# Basisboard_Klemme.net
KiCad netlist of a schematic drawn in EAGLE
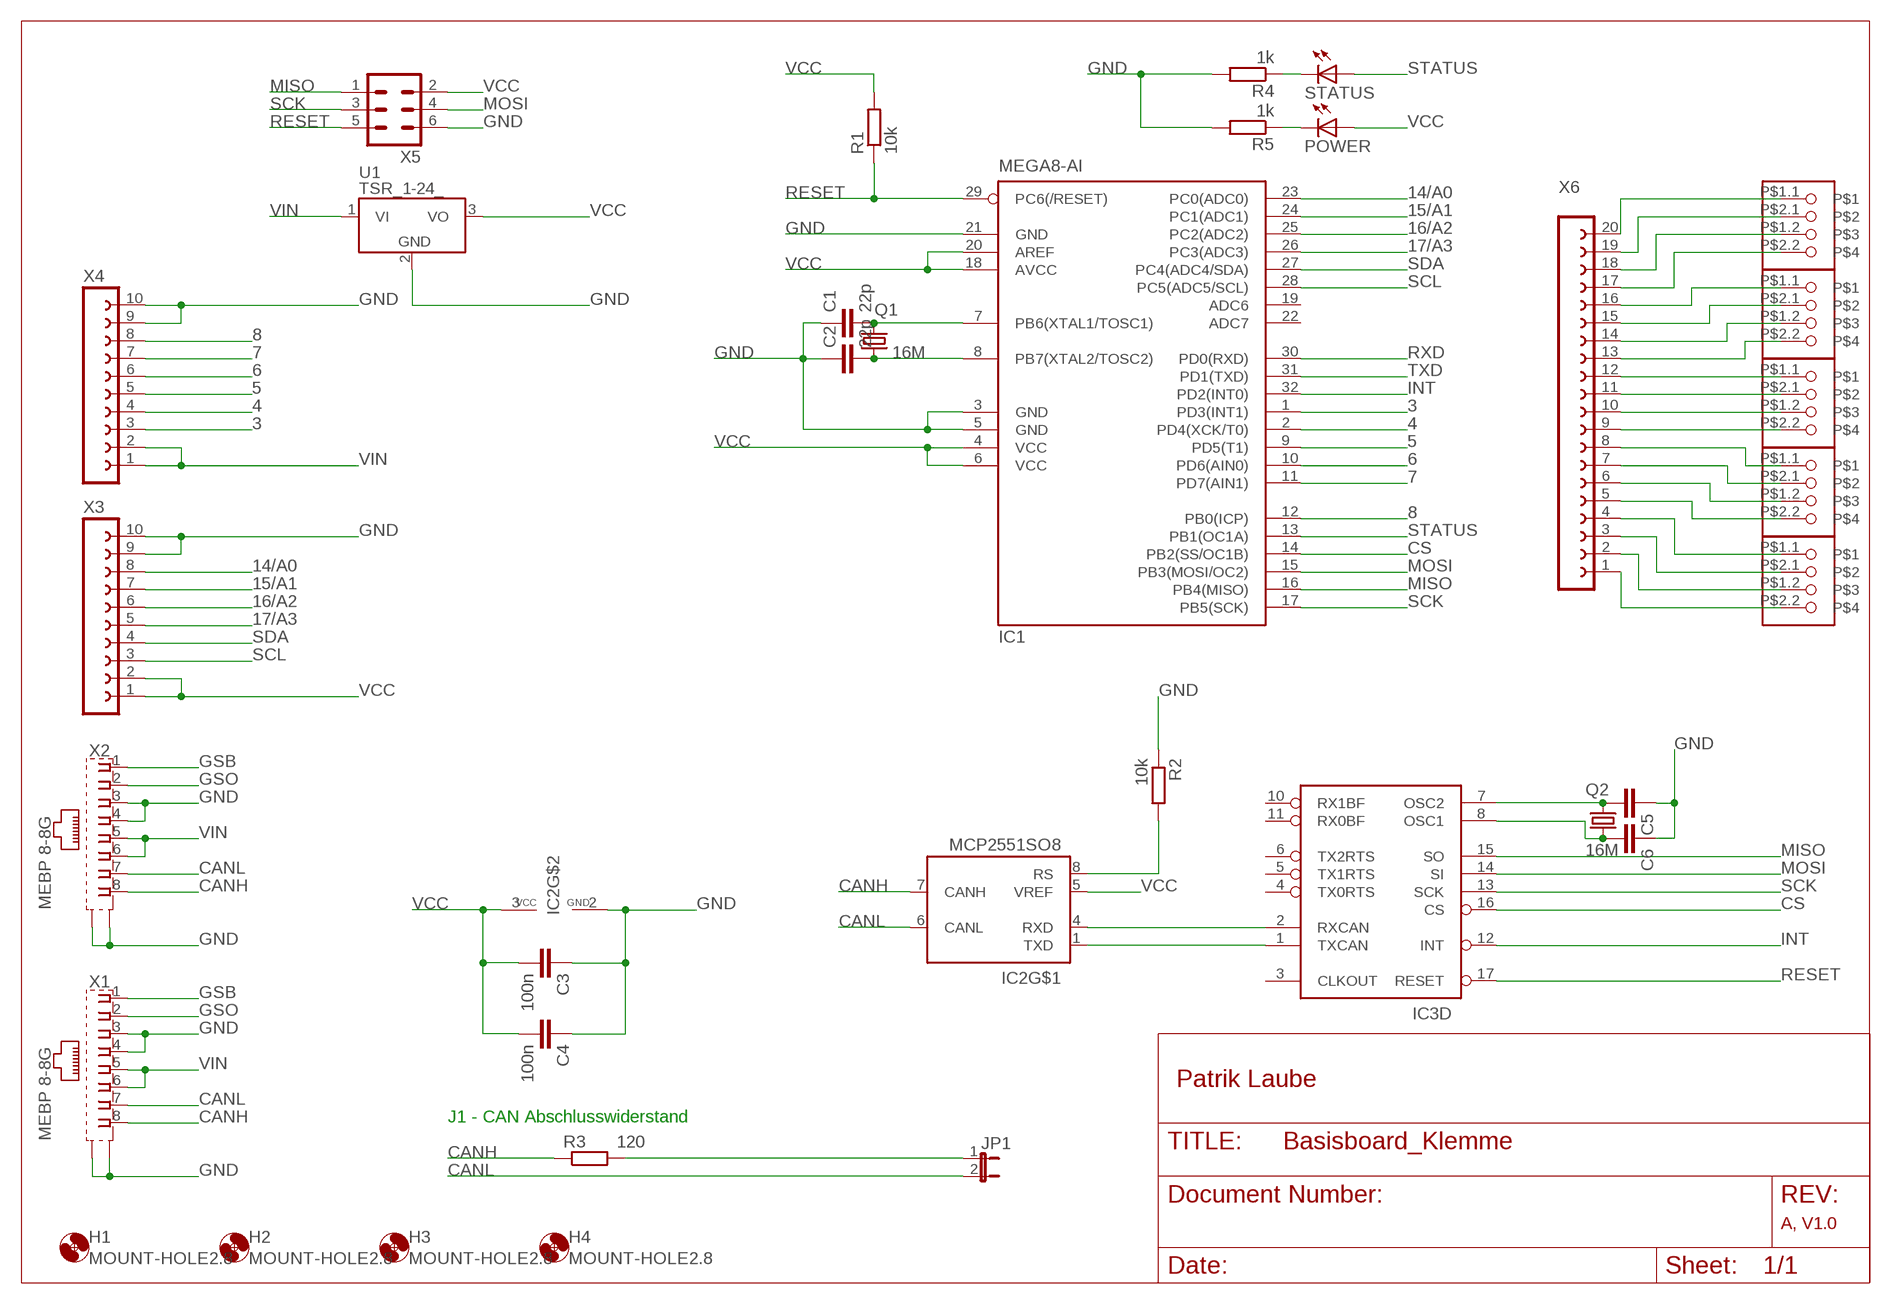
[diagram p0: schematic, sheet 1]

(export (version "E")
  (design (tool "Eeschema 10.0.6"))
  (components
    (comp (ref "C1")
      (value "22p")
      (footprint "eagle-import:C1206")
      (fields (field (name "LCSC_PART") "C313096"))
      (libsource (lib "eagle-import") (part "C-EUC1206"))
    )
    (comp (ref "C2")
      (value "22p")
      (footprint "eagle-import:C1206")
      (fields (field (name "LCSC_PART") "C313096"))
      (libsource (lib "eagle-import") (part "C-EUC1206"))
    )
    (comp (ref "C3")
      (value "100n")
      (footprint "eagle-import:C1206")
      (fields (field (name "LCSC_PART") "C24497"))
      (libsource (lib "eagle-import") (part "C-EUC1206"))
    )
    (comp (ref "C4")
      (value "100n")
      (footprint "eagle-import:C1206")
      (fields (field (name "LCSC_PART") "C24497"))
      (libsource (lib "eagle-import") (part "C-EUC1206"))
    )
    (comp (ref "C5")
      (value "C-EUC1206")
      (footprint "eagle-import:C1206")
      (fields (field (name "LCSC_PART") "C313096"))
      (libsource (lib "eagle-import") (part "C-EUC1206"))
    )
    (comp (ref "C6")
      (value "C-EUC1206")
      (footprint "eagle-import:C1206")
      (fields (field (name "LCSC_PART") "C313096"))
      (libsource (lib "eagle-import") (part "C-EUC1206"))
    )
    (comp (ref "H1")
      (value "MOUNT-HOLE2.8")
      (footprint "eagle-import:2,8")
      (libsource (lib "eagle-import") (part "MOUNT-HOLE2.8"))
    )
    (comp (ref "H2")
      (value "MOUNT-HOLE2.8")
      (footprint "eagle-import:2,8")
      (libsource (lib "eagle-import") (part "MOUNT-HOLE2.8"))
    )
    (comp (ref "H3")
      (value "MOUNT-HOLE2.8")
      (footprint "eagle-import:2,8")
      (libsource (lib "eagle-import") (part "MOUNT-HOLE2.8"))
    )
    (comp (ref "H4")
      (value "MOUNT-HOLE2.8")
      (footprint "eagle-import:2,8")
      (libsource (lib "eagle-import") (part "MOUNT-HOLE2.8"))
    )
    (comp (ref "IC1")
      (value "MEGA8-AI")
      (footprint "eagle-import:TQFP32-08")
      (fields (field (name "MPN") "ATMEGA8-16AU") (field (name "LCSC_PART") "C132230"))
      (libsource (lib "eagle-import") (part "MEGA8-AI"))
    )
    (comp (ref "IC2")
      (value "MCP2551SO8")
      (footprint "eagle-import:SO08")
      (fields (field (name "LCSC_PART") "C49558"))
      (libsource (lib "eagle-import") (part "MCP2551SO8"))
    )
    (comp (ref "IC3")
      (value "MCP2515SO")
      (footprint "eagle-import:SO-18W")
      (fields (field (name "LCSC_PART") "C153782"))
      (libsource (lib "eagle-import") (part "MCP2515SO"))
    )
    (comp (ref "JP1")
      (value "JP1E")
      (footprint "eagle-import:JP1")
      (libsource (lib "eagle-import") (part "JP1E"))
    )
    (comp (ref "POWER")
      (value "LEDCHIPLED_1206")
      (footprint "eagle-import:CHIPLED_1206")
      (fields (field (name "LCSC_PART") "C88326"))
      (libsource (lib "eagle-import") (part "LEDCHIPLED_1206"))
    )
    (comp (ref "Q1")
      (value "16M")
      (footprint "eagle-import:HC49_S")
      (libsource (lib "eagle-import") (part "CRYSTALHC49S"))
    )
    (comp (ref "Q2")
      (value "16M")
      (footprint "eagle-import:HC49_S")
      (libsource (lib "eagle-import") (part "CRYSTALHC49S"))
    )
    (comp (ref "R1")
      (value "10k")
      (footprint "eagle-import:R1206")
      (fields (field (name "LCSC_PART") " C17902"))
      (libsource (lib "eagle-import") (part "R-EU_R1206"))
    )
    (comp (ref "R2")
      (value "10k")
      (footprint "eagle-import:R1206")
      (fields (field (name "LCSC_PART") " C17902"))
      (libsource (lib "eagle-import") (part "R-EU_R1206"))
    )
    (comp (ref "R3")
      (value "120")
      (footprint "eagle-import:R1206")
      (fields (field (name "LCSC_PART") "C17909"))
      (libsource (lib "eagle-import") (part "rcl_334_R-EU_R1206"))
    )
    (comp (ref "R4")
      (value "1k")
      (footprint "eagle-import:R1206")
      (fields (field (name "LCSC_PART") "C4410"))
      (libsource (lib "eagle-import") (part "R-EU_R1206"))
    )
    (comp (ref "R5")
      (value "1k")
      (footprint "eagle-import:R1206")
      (fields (field (name "LCSC_PART") "C4410"))
      (libsource (lib "eagle-import") (part "R-EU_R1206"))
    )
    (comp (ref "STATUS")
      (value "LEDCHIPLED_1206")
      (footprint "eagle-import:CHIPLED_1206")
      (fields (field (name "LCSC_PART") "C84273"))
      (libsource (lib "eagle-import") (part "LEDCHIPLED_1206"))
    )
    (comp (ref "U$4")
      (value "AKL093-06")
      (footprint "eagle-import:AKL093-06")
      (libsource (lib "eagle-import") (part "AKL093-06"))
    )
    (comp (ref "U$5")
      (value "AKL093-06")
      (footprint "eagle-import:AKL093-06")
      (libsource (lib "eagle-import") (part "AKL093-06"))
    )
    (comp (ref "U$6")
      (value "AKL093-06")
      (footprint "eagle-import:AKL093-06")
      (libsource (lib "eagle-import") (part "AKL093-06"))
    )
    (comp (ref "U$7")
      (value "AKL093-06")
      (footprint "eagle-import:AKL093-06")
      (libsource (lib "eagle-import") (part "AKL093-06"))
    )
    (comp (ref "U$8")
      (value "AKL093-06")
      (footprint "eagle-import:AKL093-06")
      (libsource (lib "eagle-import") (part "AKL093-06"))
    )
    (comp (ref "U1")
      (value "TSR_1-24_")
      (footprint "eagle-import:TSR-1")
      (libsource (lib "eagle-import") (part "TSR_1-24_"))
    )
    (comp (ref "X1")
      (value "MEBP 8-8G")
      (footprint "eagle-import:XRJF-01A-0-D2A-010")
      (libsource (lib "eagle-import") (part "XRJFMEBP-8-8G-01A-0-D22-020"))
    )
    (comp (ref "X2")
      (value "MEBP 8-8G")
      (footprint "eagle-import:XRJF-01A-0-D2A-010")
      (libsource (lib "eagle-import") (part "XRJFMEBP-8-8G-01A-0-D22-020"))
    )
    (comp (ref "X3")
      (value "FE10-1")
      (footprint "eagle-import:FE10")
      (libsource (lib "eagle-import") (part "FE10-1"))
    )
    (comp (ref "X4")
      (value "FE10-1")
      (footprint "eagle-import:FE10")
      (libsource (lib "eagle-import") (part "FE10-1"))
    )
    (comp (ref "X5")
      (value "ML6")
      (footprint "eagle-import:ML6")
      (libsource (lib "eagle-import") (part "ML6"))
    )
    (comp (ref "X6")
      (value "FE20-1")
      (footprint "eagle-import:FE20")
      (libsource (lib "eagle-import") (part "FE20-1"))
    )
  )
  (nets
    (net (code "1") (name "/3") (class "Default")
      (node (ref "IC1") (pin "1") (pinfunction "PD3(INT1)_1") (pintype "bidirectional"))
      (node (ref "X4") (pin "3") (pinfunction "3_3") (pintype "passive"))
    )
    (net (code "2") (name "/4") (class "Default")
      (node (ref "IC1") (pin "2") (pinfunction "PD4(XCK/T0)_2") (pintype "bidirectional"))
      (node (ref "X4") (pin "4") (pinfunction "4_4") (pintype "passive"))
    )
    (net (code "3") (name "/5") (class "Default")
      (node (ref "IC1") (pin "9") (pinfunction "PD5(T1)_9") (pintype "bidirectional"))
      (node (ref "X4") (pin "5") (pinfunction "5_5") (pintype "passive"))
    )
    (net (code "4") (name "/6") (class "Default")
      (node (ref "IC1") (pin "10") (pinfunction "PD6(AIN0)_10") (pintype "bidirectional"))
      (node (ref "X4") (pin "6") (pinfunction "6_6") (pintype "passive"))
    )
    (net (code "5") (name "/7") (class "Default")
      (node (ref "IC1") (pin "11") (pinfunction "PD7(AIN1)_11") (pintype "bidirectional"))
      (node (ref "X4") (pin "7") (pinfunction "7_7") (pintype "passive"))
    )
    (net (code "6") (name "/8") (class "Default")
      (node (ref "IC1") (pin "12") (pinfunction "PB0(ICP)_12") (pintype "bidirectional"))
      (node (ref "X4") (pin "8") (pinfunction "8_8") (pintype "passive"))
    )
    (net (code "7") (name "/14{slash}A0") (class "Default")
      (node (ref "IC1") (pin "23") (pinfunction "PC0(ADC0)_23") (pintype "bidirectional"))
      (node (ref "X3") (pin "8") (pinfunction "8_8") (pintype "passive"))
    )
    (net (code "8") (name "/15{slash}A1") (class "Default")
      (node (ref "IC1") (pin "24") (pinfunction "PC1(ADC1)_24") (pintype "bidirectional"))
      (node (ref "X3") (pin "7") (pinfunction "7_7") (pintype "passive"))
    )
    (net (code "9") (name "/16{slash}A2") (class "Default")
      (node (ref "IC1") (pin "25") (pinfunction "PC2(ADC2)_25") (pintype "bidirectional"))
      (node (ref "X3") (pin "6") (pinfunction "6_6") (pintype "passive"))
    )
    (net (code "10") (name "/17{slash}A3") (class "Default")
      (node (ref "IC1") (pin "26") (pinfunction "PC3(ADC3)_26") (pintype "bidirectional"))
      (node (ref "X3") (pin "5") (pinfunction "5_5") (pintype "passive"))
    )
    (net (code "11") (name "/CANH") (class "Default")
      (node (ref "IC2") (pin "7") (pinfunction "CANH_7") (pintype "bidirectional"))
      (node (ref "R3") (pin "1") (pinfunction "1_1") (pintype "passive"))
      (node (ref "X1") (pin "8") (pinfunction "8_8") (pintype "passive"))
      (node (ref "X2") (pin "8") (pinfunction "8_8") (pintype "passive"))
    )
    (net (code "12") (name "/CANL") (class "Default")
      (node (ref "IC2") (pin "6") (pinfunction "CANL_6") (pintype "bidirectional"))
      (node (ref "JP1") (pin "2") (pinfunction "2_2") (pintype "passive"))
      (node (ref "X1") (pin "7") (pinfunction "7_7") (pintype "passive"))
      (node (ref "X2") (pin "7") (pinfunction "7_7") (pintype "passive"))
    )
    (net (code "13") (name "/CS") (class "Default")
      (node (ref "IC1") (pin "14") (pinfunction "PB2(SS/OC1B)_14") (pintype "bidirectional"))
      (node (ref "IC3") (pin "16") (pinfunction "CS_16") (pintype "input"))
    )
    (net (code "14") (name "/GND") (class "Default")
      (node (ref "C1") (pin "1") (pinfunction "1_1") (pintype "passive"))
      (node (ref "C2") (pin "1") (pinfunction "1_1") (pintype "passive"))
      (node (ref "C3") (pin "1") (pinfunction "1_1") (pintype "passive"))
      (node (ref "C4") (pin "1") (pinfunction "1_1") (pintype "passive"))
      (node (ref "C5") (pin "1") (pinfunction "1_1") (pintype "passive"))
      (node (ref "C6") (pin "1") (pinfunction "1_1") (pintype "passive"))
      (node (ref "IC1") (pin "21") (pinfunction "GND_21") (pintype "power_in"))
      (node (ref "IC1") (pin "3") (pinfunction "GND_3") (pintype "power_in"))
      (node (ref "IC1") (pin "5") (pinfunction "GND_5") (pintype "power_in"))
      (node (ref "IC2") (pin "2") (pinfunction "GND_2") (pintype "power_in"))
      (node (ref "R2") (pin "1") (pinfunction "1_1") (pintype "passive"))
      (node (ref "R4") (pin "2") (pinfunction "2_2") (pintype "passive"))
      (node (ref "R5") (pin "2") (pinfunction "2_2") (pintype "passive"))
      (node (ref "U1") (pin "2") (pinfunction "GND_2") (pintype "power_in"))
      (node (ref "X1") (pin "3") (pinfunction "3_3") (pintype "passive"))
      (node (ref "X1") (pin "4") (pinfunction "4_4") (pintype "passive"))
      (node (ref "X1") (pin "S1") (pinfunction "S_S1") (pintype "passive"))
      (node (ref "X1") (pin "S2") (pinfunction "S_S2") (pintype "passive"))
      (node (ref "X2") (pin "3") (pinfunction "3_3") (pintype "passive"))
      (node (ref "X2") (pin "4") (pinfunction "4_4") (pintype "passive"))
      (node (ref "X2") (pin "S1") (pinfunction "S_S1") (pintype "passive"))
      (node (ref "X2") (pin "S2") (pinfunction "S_S2") (pintype "passive"))
      (node (ref "X3") (pin "10") (pinfunction "10_10") (pintype "passive"))
      (node (ref "X3") (pin "9") (pinfunction "9_9") (pintype "passive"))
      (node (ref "X4") (pin "10") (pinfunction "10_10") (pintype "passive"))
      (node (ref "X4") (pin "9") (pinfunction "9_9") (pintype "passive"))
      (node (ref "X5") (pin "6") (pinfunction "6_6") (pintype "passive"))
    )
    (net (code "15") (name "/GSB") (class "Default")
      (node (ref "X1") (pin "1") (pinfunction "1_1") (pintype "passive"))
      (node (ref "X2") (pin "1") (pinfunction "1_1") (pintype "passive"))
    )
    (net (code "16") (name "/GSO") (class "Default")
      (node (ref "X1") (pin "2") (pinfunction "2_2") (pintype "passive"))
      (node (ref "X2") (pin "2") (pinfunction "2_2") (pintype "passive"))
    )
    (net (code "17") (name "/INT") (class "Default")
      (node (ref "IC1") (pin "32") (pinfunction "PD2(INT0)_32") (pintype "bidirectional"))
      (node (ref "IC3") (pin "12") (pinfunction "INT_12") (pintype "output"))
    )
    (net (code "18") (name "/MISO") (class "Default")
      (node (ref "IC1") (pin "16") (pinfunction "PB4(MISO)_16") (pintype "bidirectional"))
      (node (ref "IC3") (pin "15") (pinfunction "SO_15") (pintype "output"))
      (node (ref "X5") (pin "1") (pinfunction "1_1") (pintype "passive"))
    )
    (net (code "19") (name "/MOSI") (class "Default")
      (node (ref "IC1") (pin "15") (pinfunction "PB3(MOSI/OC2)_15") (pintype "bidirectional"))
      (node (ref "IC3") (pin "14") (pinfunction "SI_14") (pintype "input"))
      (node (ref "X5") (pin "4") (pinfunction "4_4") (pintype "passive"))
    )
    (net (code "20") (name "/RESET") (class "Default")
      (node (ref "IC1") (pin "29") (pinfunction "PC6(/RESET)_29") (pintype "bidirectional"))
      (node (ref "IC3") (pin "17") (pinfunction "RESET_17") (pintype "input"))
      (node (ref "R1") (pin "1") (pinfunction "1_1") (pintype "passive"))
      (node (ref "X5") (pin "5") (pinfunction "5_5") (pintype "passive"))
    )
    (net (code "21") (name "/RXD") (class "Default")
      (node (ref "IC1") (pin "30") (pinfunction "PD0(RXD)_30") (pintype "bidirectional"))
    )
    (net (code "22") (name "/SCK") (class "Default")
      (node (ref "IC1") (pin "17") (pinfunction "PB5(SCK)_17") (pintype "bidirectional"))
      (node (ref "IC3") (pin "13") (pinfunction "SCK_13") (pintype "input"))
      (node (ref "X5") (pin "3") (pinfunction "3_3") (pintype "passive"))
    )
    (net (code "23") (name "/SCL") (class "Default")
      (node (ref "IC1") (pin "28") (pinfunction "PC5(ADC5/SCL)_28") (pintype "bidirectional"))
      (node (ref "X3") (pin "3") (pinfunction "3_3") (pintype "passive"))
    )
    (net (code "24") (name "/SDA") (class "Default")
      (node (ref "IC1") (pin "27") (pinfunction "PC4(ADC4/SDA)_27") (pintype "bidirectional"))
      (node (ref "X3") (pin "4") (pinfunction "4_4") (pintype "passive"))
    )
    (net (code "25") (name "/STATUS") (class "Default")
      (node (ref "IC1") (pin "13") (pinfunction "PB1(OC1A)_13") (pintype "bidirectional"))
      (node (ref "STATUS") (pin "A") (pinfunction "A_A") (pintype "passive"))
    )
    (net (code "26") (name "/TXD") (class "Default")
      (node (ref "IC1") (pin "31") (pinfunction "PD1(TXD)_31") (pintype "bidirectional"))
    )
    (net (code "27") (name "/VCC") (class "Default")
      (node (ref "C3") (pin "2") (pinfunction "2_2") (pintype "passive"))
      (node (ref "C4") (pin "2") (pinfunction "2_2") (pintype "passive"))
      (node (ref "IC1") (pin "18") (pinfunction "AVCC_18") (pintype "power_in"))
      (node (ref "IC1") (pin "20") (pinfunction "AREF_20") (pintype "passive"))
      (node (ref "IC1") (pin "4") (pinfunction "VCC_4") (pintype "power_in"))
      (node (ref "IC1") (pin "6") (pinfunction "VCC_6") (pintype "power_in"))
      (node (ref "IC2") (pin "3") (pinfunction "VCC_3") (pintype "power_in"))
      (node (ref "IC2") (pin "5") (pinfunction "VREF_5") (pintype "bidirectional"))
      (node (ref "POWER") (pin "A") (pinfunction "A_A") (pintype "passive"))
      (node (ref "R1") (pin "2") (pinfunction "2_2") (pintype "passive"))
      (node (ref "U1") (pin "3") (pinfunction "VO_3") (pintype "power_in"))
      (node (ref "X3") (pin "1") (pinfunction "1_1") (pintype "passive"))
      (node (ref "X3") (pin "2") (pinfunction "2_2") (pintype "passive"))
      (node (ref "X5") (pin "2") (pinfunction "2_2") (pintype "passive"))
    )
    (net (code "28") (name "/VIN") (class "Default")
      (node (ref "U1") (pin "1") (pinfunction "VI_1") (pintype "power_in"))
      (node (ref "X1") (pin "5") (pinfunction "5_5") (pintype "passive"))
      (node (ref "X1") (pin "6") (pinfunction "6_6") (pintype "passive"))
      (node (ref "X2") (pin "5") (pinfunction "5_5") (pintype "passive"))
      (node (ref "X2") (pin "6") (pinfunction "6_6") (pintype "passive"))
      (node (ref "X4") (pin "1") (pinfunction "1_1") (pintype "passive"))
      (node (ref "X4") (pin "2") (pinfunction "2_2") (pintype "passive"))
    )
    (net (code "29") (name "Net-(IC1-PB6(XTAL1{slash}TOSC1))") (class "Default")
      (node (ref "C1") (pin "2") (pinfunction "2_2") (pintype "passive"))
      (node (ref "IC1") (pin "7") (pinfunction "PB6(XTAL1/TOSC1)_7") (pintype "bidirectional"))
      (node (ref "Q1") (pin "2") (pinfunction "2_2") (pintype "passive"))
    )
    (net (code "30") (name "Net-(IC1-PB7(XTAL2{slash}TOSC2))") (class "Default")
      (node (ref "C2") (pin "2") (pinfunction "2_2") (pintype "passive"))
      (node (ref "IC1") (pin "8") (pinfunction "PB7(XTAL2/TOSC2)_8") (pintype "bidirectional"))
      (node (ref "Q1") (pin "1") (pinfunction "1_1") (pintype "passive"))
    )
    (net (code "31") (name "Net-(IC2A-RS)") (class "Default")
      (node (ref "IC2") (pin "8") (pinfunction "RS_8") (pintype "bidirectional"))
      (node (ref "R2") (pin "2") (pinfunction "2_2") (pintype "passive"))
    )
    (net (code "32") (name "Net-(IC2A-RXD)") (class "Default")
      (node (ref "IC2") (pin "4") (pinfunction "RXD_4") (pintype "bidirectional"))
      (node (ref "IC3") (pin "2") (pinfunction "RXCAN_2") (pintype "input"))
    )
    (net (code "33") (name "Net-(IC2A-TXD)") (class "Default")
      (node (ref "IC2") (pin "1") (pinfunction "TXD_1") (pintype "bidirectional"))
      (node (ref "IC3") (pin "1") (pinfunction "TXCAN_1") (pintype "output"))
    )
    (net (code "34") (name "Net-(IC3A-OSC1)") (class "Default")
      (node (ref "C6") (pin "2") (pinfunction "2_2") (pintype "passive"))
      (node (ref "IC3") (pin "8") (pinfunction "OSC1_8") (pintype "input"))
      (node (ref "Q2") (pin "2") (pinfunction "2_2") (pintype "passive"))
    )
    (net (code "35") (name "Net-(IC3A-OSC2)") (class "Default")
      (node (ref "C5") (pin "2") (pinfunction "2_2") (pintype "passive"))
      (node (ref "IC3") (pin "7") (pinfunction "OSC2_7") (pintype "input"))
      (node (ref "Q2") (pin "1") (pinfunction "1_1") (pintype "passive"))
    )
    (net (code "36") (name "Net-(JP1-Pad1)") (class "Default")
      (node (ref "JP1") (pin "1") (pinfunction "1_1") (pintype "passive"))
      (node (ref "R3") (pin "2") (pinfunction "2_2") (pintype "passive"))
    )
    (net (code "37") (name "Net-(POWER-PadC)") (class "Default")
      (node (ref "POWER") (pin "C") (pinfunction "C_C") (pintype "passive"))
      (node (ref "R5") (pin "1") (pinfunction "1_1") (pintype "passive"))
    )
    (net (code "38") (name "Net-(R4-Pad1)") (class "Default")
      (node (ref "R4") (pin "1") (pinfunction "1_1") (pintype "passive"))
      (node (ref "STATUS") (pin "C") (pinfunction "C_C") (pintype "passive"))
    )
    (net (code "39") (name "Net-(U$4-P$1)") (class "Default")
      (node (ref "U$4") (pin "P$1.1") (pinfunction "P$1_P$1.1") (pintype "bidirectional"))
      (node (ref "X6") (pin "12") (pinfunction "12_12") (pintype "passive"))
    )
    (net (code "40") (name "Net-(U$4-P$2)") (class "Default")
      (node (ref "U$4") (pin "P$2.1") (pinfunction "P$2_P$2.1") (pintype "bidirectional"))
      (node (ref "X6") (pin "11") (pinfunction "11_11") (pintype "passive"))
    )
    (net (code "41") (name "Net-(U$4-P$3)") (class "Default")
      (node (ref "U$4") (pin "P$1.2") (pinfunction "P$3_P$1.2") (pintype "bidirectional"))
      (node (ref "X6") (pin "10") (pinfunction "10_10") (pintype "passive"))
    )
    (net (code "42") (name "Net-(U$4-P$4)") (class "Default")
      (node (ref "U$4") (pin "P$2.2") (pinfunction "P$4_P$2.2") (pintype "bidirectional"))
      (node (ref "X6") (pin "9") (pinfunction "9_9") (pintype "passive"))
    )
    (net (code "43") (name "Net-(U$5-P$1)") (class "Default")
      (node (ref "U$5") (pin "P$1.1") (pinfunction "P$1_P$1.1") (pintype "bidirectional"))
      (node (ref "X6") (pin "16") (pinfunction "16_16") (pintype "passive"))
    )
    (net (code "44") (name "Net-(U$5-P$2)") (class "Default")
      (node (ref "U$5") (pin "P$2.1") (pinfunction "P$2_P$2.1") (pintype "bidirectional"))
      (node (ref "X6") (pin "15") (pinfunction "15_15") (pintype "passive"))
    )
    (net (code "45") (name "Net-(U$5-P$3)") (class "Default")
      (node (ref "U$5") (pin "P$1.2") (pinfunction "P$3_P$1.2") (pintype "bidirectional"))
      (node (ref "X6") (pin "14") (pinfunction "14_14") (pintype "passive"))
    )
    (net (code "46") (name "Net-(U$5-P$4)") (class "Default")
      (node (ref "U$5") (pin "P$2.2") (pinfunction "P$4_P$2.2") (pintype "bidirectional"))
      (node (ref "X6") (pin "13") (pinfunction "13_13") (pintype "passive"))
    )
    (net (code "47") (name "Net-(U$6-P$1)") (class "Default")
      (node (ref "U$6") (pin "P$1.1") (pinfunction "P$1_P$1.1") (pintype "bidirectional"))
      (node (ref "X6") (pin "8") (pinfunction "8_8") (pintype "passive"))
    )
    (net (code "48") (name "Net-(U$6-P$2)") (class "Default")
      (node (ref "U$6") (pin "P$2.1") (pinfunction "P$2_P$2.1") (pintype "bidirectional"))
      (node (ref "X6") (pin "7") (pinfunction "7_7") (pintype "passive"))
    )
    (net (code "49") (name "Net-(U$6-P$3)") (class "Default")
      (node (ref "U$6") (pin "P$1.2") (pinfunction "P$3_P$1.2") (pintype "bidirectional"))
      (node (ref "X6") (pin "6") (pinfunction "6_6") (pintype "passive"))
    )
    (net (code "50") (name "Net-(U$6-P$4)") (class "Default")
      (node (ref "U$6") (pin "P$2.2") (pinfunction "P$4_P$2.2") (pintype "bidirectional"))
      (node (ref "X6") (pin "5") (pinfunction "5_5") (pintype "passive"))
    )
    (net (code "51") (name "Net-(U$7-P$1)") (class "Default")
      (node (ref "U$7") (pin "P$1.1") (pinfunction "P$1_P$1.1") (pintype "bidirectional"))
      (node (ref "X6") (pin "4") (pinfunction "4_4") (pintype "passive"))
    )
    (net (code "52") (name "Net-(U$7-P$2)") (class "Default")
      (node (ref "U$7") (pin "P$2.1") (pinfunction "P$2_P$2.1") (pintype "bidirectional"))
      (node (ref "X6") (pin "3") (pinfunction "3_3") (pintype "passive"))
    )
    (net (code "53") (name "Net-(U$7-P$3)") (class "Default")
      (node (ref "U$7") (pin "P$1.2") (pinfunction "P$3_P$1.2") (pintype "bidirectional"))
      (node (ref "X6") (pin "2") (pinfunction "2_2") (pintype "passive"))
    )
    (net (code "54") (name "Net-(U$7-P$4)") (class "Default")
      (node (ref "U$7") (pin "P$2.2") (pinfunction "P$4_P$2.2") (pintype "bidirectional"))
      (node (ref "X6") (pin "1") (pinfunction "1_1") (pintype "passive"))
    )
    (net (code "55") (name "Net-(U$8-P$1)") (class "Default")
      (node (ref "U$8") (pin "P$1.1") (pinfunction "P$1_P$1.1") (pintype "bidirectional"))
      (node (ref "X6") (pin "20") (pinfunction "20_20") (pintype "passive"))
    )
    (net (code "56") (name "Net-(U$8-P$2)") (class "Default")
      (node (ref "U$8") (pin "P$2.1") (pinfunction "P$2_P$2.1") (pintype "bidirectional"))
      (node (ref "X6") (pin "19") (pinfunction "19_19") (pintype "passive"))
    )
    (net (code "57") (name "Net-(U$8-P$3)") (class "Default")
      (node (ref "U$8") (pin "P$1.2") (pinfunction "P$3_P$1.2") (pintype "bidirectional"))
      (node (ref "X6") (pin "18") (pinfunction "18_18") (pintype "passive"))
    )
    (net (code "58") (name "Net-(U$8-P$4)") (class "Default")
      (node (ref "U$8") (pin "P$2.2") (pinfunction "P$4_P$2.2") (pintype "bidirectional"))
      (node (ref "X6") (pin "17") (pinfunction "17_17") (pintype "passive"))
    )
    (net (code "59") (name "unconnected-(IC1-ADC6-Pad19)") (class "Default")
      (node (ref "IC1") (pin "19") (pinfunction "ADC6_19") (pintype "bidirectional"))
    )
    (net (code "60") (name "unconnected-(IC1-ADC7-Pad22)") (class "Default")
      (node (ref "IC1") (pin "22") (pinfunction "ADC7_22") (pintype "bidirectional"))
    )
    (net (code "61") (name "unconnected-(IC3A-CLKOUT-Pad3)") (class "Default")
      (node (ref "IC3") (pin "3") (pinfunction "CLKOUT_3") (pintype "output"))
    )
    (net (code "62") (name "unconnected-(IC3A-RX0BF-Pad11)") (class "Default")
      (node (ref "IC3") (pin "11") (pinfunction "RX0BF_11") (pintype "output"))
    )
    (net (code "63") (name "unconnected-(IC3A-RX1BF-Pad10)") (class "Default")
      (node (ref "IC3") (pin "10") (pinfunction "RX1BF_10") (pintype "output"))
    )
    (net (code "64") (name "unconnected-(IC3A-TX0RTS-Pad4)") (class "Default")
      (node (ref "IC3") (pin "4") (pinfunction "TX0RTS_4") (pintype "input"))
    )
    (net (code "65") (name "unconnected-(IC3A-TX1RTS-Pad5)") (class "Default")
      (node (ref "IC3") (pin "5") (pinfunction "TX1RTS_5") (pintype "input"))
    )
    (net (code "66") (name "unconnected-(IC3A-TX2RTS-Pad6)") (class "Default")
      (node (ref "IC3") (pin "6") (pinfunction "TX2RTS_6") (pintype "input"))
    )
  )
)
